# Motor_Driver.net
KiCad netlist of a schematic drawn in Altium Designer
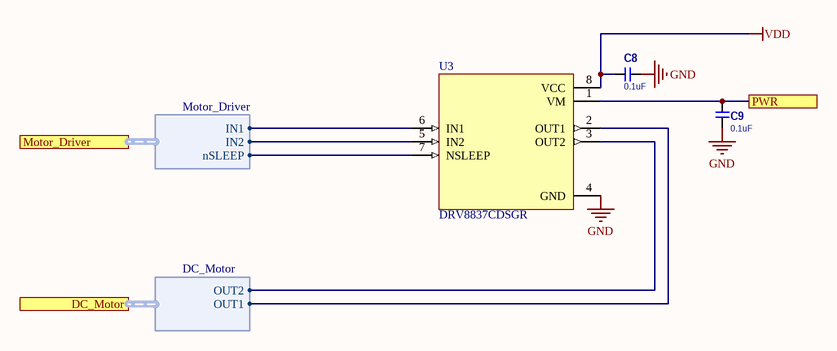
[diagram p0: Motor_Driver.SchDoc]

(export (version "E")
  (design (tool "Eeschema 10.0.6"))
  (components
    (comp (ref "C8")
      (value "0.1uF")
      (footprint "0603-C")
      (description "CAP")
      (fields
        (field (name "MANUFACTURER") "TDK EPCOS")
        (field (name "MANUFACTURER PART NUMBER") "B37941K9105K62")
      )
      (libsource (lib "Safety_Lock") (part "CAP"))
    )
    (comp (ref "C9")
      (value "0.1uF")
      (footprint "0603-C")
      (description "CAP")
      (fields
        (field (name "MANUFACTURER") "TDK EPCOS")
        (field (name "MANUFACTURER PART NUMBER") "B37941K9105K62")
      )
      (libsource (lib "Safety_Lock") (part "CAP"))
    )
    (comp (ref "U3")
      (value "DRV8837CDSGR")
      (footprint "SON50P200X200X80-9N")
      (description "11-V, 1-A H-bridge motor driver 8-WSON -40 to 85")
      (fields (field (name "MF") "Texas Instruments"))
      (libsource (lib "Safety_Lock") (part "DRV8837CDSGR"))
    )
  )
  (nets
    (net (code "3") (name "/IN1") (class "Default")
      (node (ref "U3") (pin "6") (pinfunction "IN1_6") (pintype "input"))
    )
    (net (code "4") (name "/IN2") (class "Default")
      (node (ref "U3") (pin "5") (pinfunction "IN2_5") (pintype "input"))
    )
    (net (code "5") (name "/OUT1") (class "Default")
      (node (ref "U3") (pin "2") (pinfunction "OUT1_2") (pintype "output"))
    )
    (net (code "6") (name "/OUT2") (class "Default")
      (node (ref "U3") (pin "3") (pinfunction "OUT2_3") (pintype "output"))
    )
    (net (code "7") (name "/PWR") (class "Default")
      (node (ref "C9") (pin "1") (pinfunction "1_1") (pintype "passive"))
      (node (ref "U3") (pin "1") (pinfunction "VM_1") (pintype "power_in"))
    )
    (net (code "8") (name "/nSLEEP") (class "Default")
      (node (ref "U3") (pin "7") (pinfunction "NSLEEP_7") (pintype "input"))
    )
    (net (code "11") (name "GND") (class "Default")
      (node (ref "C8") (pin "2") (pinfunction "2_2") (pintype "passive"))
      (node (ref "C9") (pin "2") (pinfunction "2_2") (pintype "passive"))
      (node (ref "U3") (pin "4") (pinfunction "GND_4") (pintype "power_in"))
    )
    (net (code "12") (name "VDD") (class "Default")
      (node (ref "C8") (pin "1") (pinfunction "1_1") (pintype "passive"))
      (node (ref "U3") (pin "8") (pinfunction "VCC_8") (pintype "power_in"))
    )
  )
)
